# Digital_Interfaces.net
KiCad netlist of a schematic drawn in Altium Designer
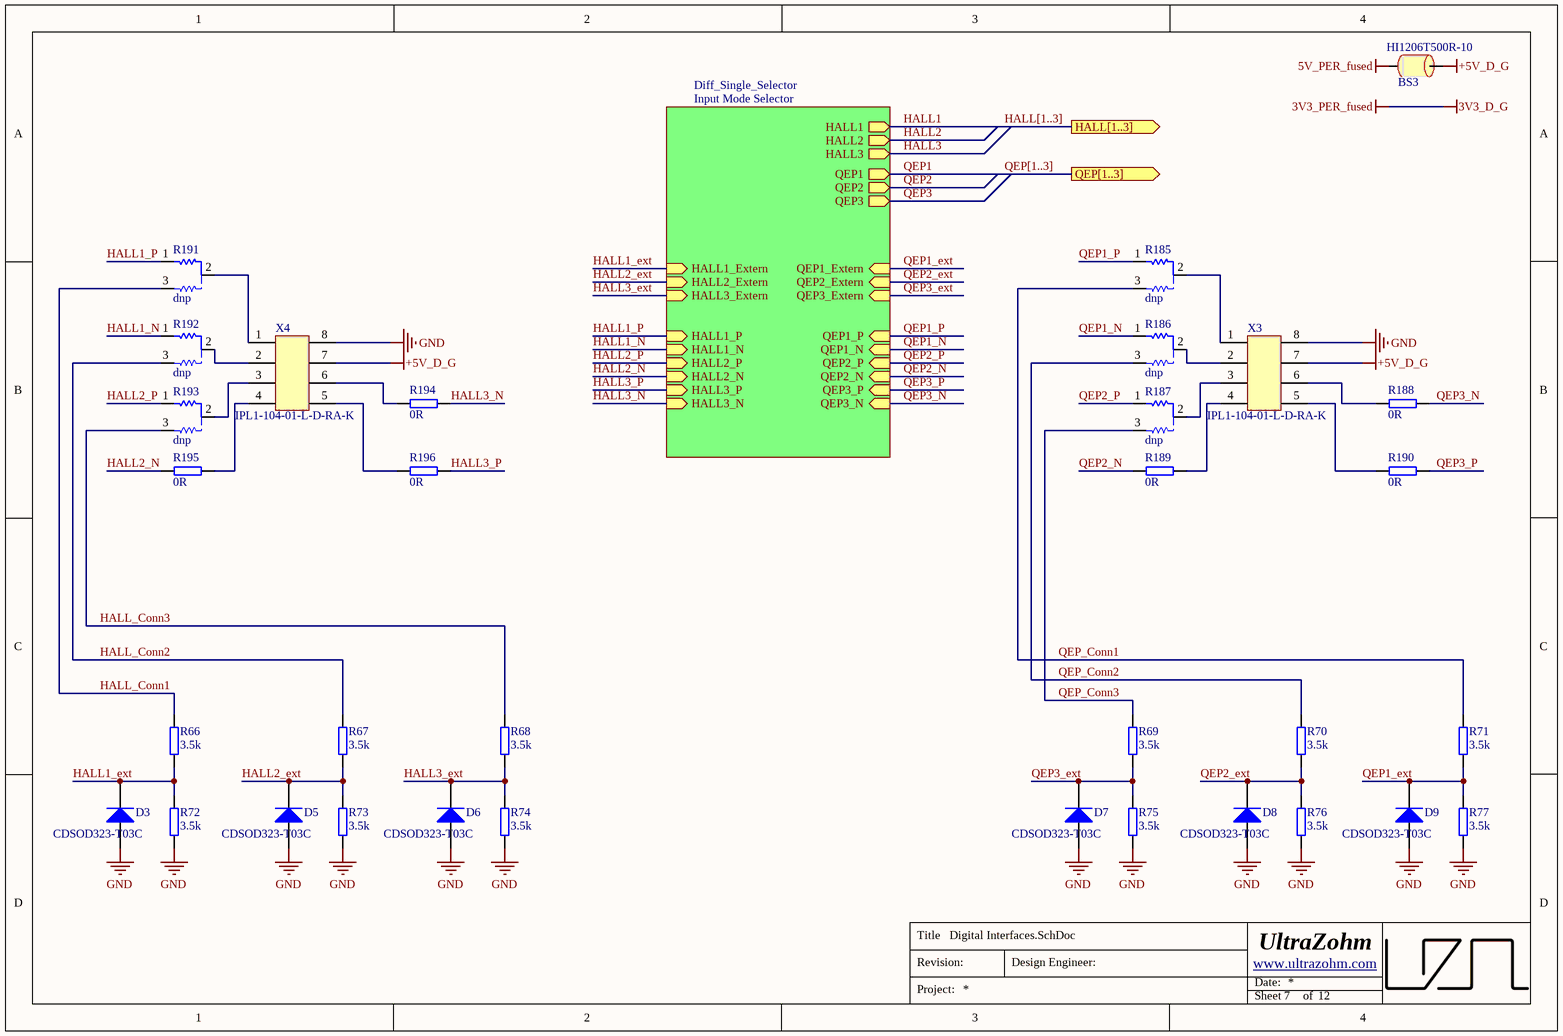
[diagram p0: Digital Interfaces.SchDoc]

(export (version "E")
  (design (tool "Eeschema 10.0.6"))
  (components
    (comp (ref "BS3")
      (value "HI1206T500R-10")
      (footprint "RES_1206")
      (description "Ferrite bead 6A")
      (fields (field (name "MF") "Laird"))
      (libsource (lib "Componentes_SOC") (part "Bead"))
    )
    (comp (ref "D3")
      (value "CDSOD323-T03C")
      (footprint "SOD-323")
      (description "TVS DIODE 3.3V 19V SOD323")
      (fields (field (name "MF") "Bourns"))
      (libsource (lib "Componentes_SOC") (part "Diodo TVS"))
    )
    (comp (ref "D5")
      (value "CDSOD323-T03C")
      (footprint "SOD-323")
      (description "TVS DIODE 3.3V 19V SOD323")
      (fields (field (name "MF") "Bourns"))
      (libsource (lib "Componentes_SOC") (part "Diodo TVS"))
    )
    (comp (ref "D6")
      (value "CDSOD323-T03C")
      (footprint "SOD-323")
      (description "TVS DIODE 3.3V 19V SOD323")
      (fields (field (name "MF") "Bourns"))
      (libsource (lib "Componentes_SOC") (part "Diodo TVS"))
    )
    (comp (ref "D7")
      (value "CDSOD323-T03C")
      (footprint "SOD-323")
      (description "TVS DIODE 3.3V 19V SOD323")
      (fields (field (name "MF") "Bourns"))
      (libsource (lib "Componentes_SOC") (part "Diodo TVS"))
    )
    (comp (ref "D8")
      (value "CDSOD323-T03C")
      (footprint "SOD-323")
      (description "TVS DIODE 3.3V 19V SOD323")
      (fields (field (name "MF") "Bourns"))
      (libsource (lib "Componentes_SOC") (part "Diodo TVS"))
    )
    (comp (ref "D9")
      (value "CDSOD323-T03C")
      (footprint "SOD-323")
      (description "TVS DIODE 3.3V 19V SOD323")
      (fields (field (name "MF") "Bourns"))
      (libsource (lib "Componentes_SOC") (part "Diodo TVS"))
    )
    (comp (ref "R66")
      (value "3.5k")
      (footprint "RESC1608X06N")
      (libsource (lib "UltraZohm_ADC") (part "R_0603"))
    )
    (comp (ref "R67")
      (value "3.5k")
      (footprint "RESC1608X06N")
      (libsource (lib "UltraZohm_ADC") (part "R_0603"))
    )
    (comp (ref "R68")
      (value "3.5k")
      (footprint "RESC1608X06N")
      (libsource (lib "UltraZohm_ADC") (part "R_0603"))
    )
    (comp (ref "R69")
      (value "3.5k")
      (footprint "RESC1608X06N")
      (libsource (lib "UltraZohm_ADC") (part "R_0603"))
    )
    (comp (ref "R70")
      (value "3.5k")
      (footprint "RESC1608X06N")
      (libsource (lib "UltraZohm_ADC") (part "R_0603"))
    )
    (comp (ref "R71")
      (value "3.5k")
      (footprint "RESC1608X06N")
      (libsource (lib "UltraZohm_ADC") (part "R_0603"))
    )
    (comp (ref "R72")
      (value "3.5k")
      (footprint "RESC1608X06N")
      (libsource (lib "UltraZohm_ADC") (part "R_0603"))
    )
    (comp (ref "R73")
      (value "3.5k")
      (footprint "RESC1608X06N")
      (libsource (lib "UltraZohm_ADC") (part "R_0603"))
    )
    (comp (ref "R74")
      (value "3.5k")
      (footprint "RESC1608X06N")
      (libsource (lib "UltraZohm_ADC") (part "R_0603"))
    )
    (comp (ref "R75")
      (value "3.5k")
      (footprint "RESC1608X06N")
      (libsource (lib "UltraZohm_ADC") (part "R_0603"))
    )
    (comp (ref "R76")
      (value "3.5k")
      (footprint "RESC1608X06N")
      (libsource (lib "UltraZohm_ADC") (part "R_0603"))
    )
    (comp (ref "R77")
      (value "3.5k")
      (footprint "RESC1608X06N")
      (libsource (lib "UltraZohm_ADC") (part "R_0603"))
    )
    (comp (ref "R185")
      (value "dnp")
      (footprint "0603_Config")
      (fields
        (field (name "MPN") "MCWR06X1002FTL")
        (field (name "MF") "Multicomp")
        (field (name "VOLTAGE") "50V")
        (field (name "CREATED") "2018_09_04_AGeiger")
      )
      (libsource (lib "Componentes_SOC") (part "R_config"))
    )
    (comp (ref "R186")
      (value "dnp")
      (footprint "0603_Config")
      (fields
        (field (name "MPN") "MCWR06X1002FTL")
        (field (name "MF") "Multicomp")
        (field (name "VOLTAGE") "50V")
        (field (name "CREATED") "2018_09_04_AGeiger")
      )
      (libsource (lib "Componentes_SOC") (part "R_config"))
    )
    (comp (ref "R187")
      (value "dnp")
      (footprint "0603_Config")
      (fields
        (field (name "MPN") "MCWR06X1002FTL")
        (field (name "MF") "Multicomp")
        (field (name "VOLTAGE") "50V")
        (field (name "CREATED") "2018_09_04_AGeiger")
      )
      (libsource (lib "Componentes_SOC") (part "R_config"))
    )
    (comp (ref "R188")
      (value "0R")
      (footprint "RESC1608X06N")
      (fields (field (name "MF") "Vishay") (field (name "MPN") "CRCW06030000Z0EAC"))
      (libsource (lib "UltraZohm_ADC") (part "R_0603"))
    )
    (comp (ref "R189")
      (value "0R")
      (footprint "RESC1608X06N")
      (fields (field (name "MF") "Vishay") (field (name "MPN") "CRCW06030000Z0EAC"))
      (libsource (lib "UltraZohm_ADC") (part "R_0603"))
    )
    (comp (ref "R190")
      (value "0R")
      (footprint "RESC1608X06N")
      (fields (field (name "MF") "Vishay") (field (name "MPN") "CRCW06030000Z0EAC"))
      (libsource (lib "UltraZohm_ADC") (part "R_0603"))
    )
    (comp (ref "R191")
      (value "dnp")
      (footprint "0603_Config")
      (fields
        (field (name "MPN") "MCWR06X1002FTL")
        (field (name "MF") "Multicomp")
        (field (name "VOLTAGE") "50V")
        (field (name "CREATED") "2018_09_04_AGeiger")
      )
      (libsource (lib "Componentes_SOC") (part "R_config"))
    )
    (comp (ref "R192")
      (value "dnp")
      (footprint "0603_Config")
      (fields
        (field (name "MPN") "MCWR06X1002FTL")
        (field (name "MF") "Multicomp")
        (field (name "VOLTAGE") "50V")
        (field (name "CREATED") "2018_09_04_AGeiger")
      )
      (libsource (lib "Componentes_SOC") (part "R_config"))
    )
    (comp (ref "R193")
      (value "dnp")
      (footprint "0603_Config")
      (fields
        (field (name "MPN") "MCWR06X1002FTL")
        (field (name "MF") "Multicomp")
        (field (name "VOLTAGE") "50V")
        (field (name "CREATED") "2018_09_04_AGeiger")
      )
      (libsource (lib "Componentes_SOC") (part "R_config"))
    )
    (comp (ref "R194")
      (value "0R")
      (footprint "RESC1608X06N")
      (fields (field (name "MF") "Vishay") (field (name "MPN") "CRCW06030000Z0EAC"))
      (libsource (lib "UltraZohm_ADC") (part "R_0603"))
    )
    (comp (ref "R195")
      (value "0R")
      (footprint "RESC1608X06N")
      (fields (field (name "MF") "Vishay") (field (name "MPN") "CRCW06030000Z0EAC"))
      (libsource (lib "UltraZohm_ADC") (part "R_0603"))
    )
    (comp (ref "R196")
      (value "0R")
      (footprint "RESC1608X06N")
      (fields (field (name "MF") "Vishay") (field (name "MPN") "CRCW06030000Z0EAC"))
      (libsource (lib "UltraZohm_ADC") (part "R_0603"))
    )
    (comp (ref "X3")
      (value "IPL1-104-01-L-D-RA-K")
      (footprint "Conector 4x2 TH Horizontal")
      (description "CONN HEADER R/A 8POS 2.54MM Through Hole")
      (fields (field (name "MF") "Samtec"))
      (libsource (lib "Componentes_SOC") (part "Conector 4x2 Horizontal"))
    )
    (comp (ref "X4")
      (value "IPL1-104-01-L-D-RA-K")
      (footprint "Conector 4x2 TH Horizontal")
      (description "CONN HEADER R/A 8POS 2.54MM Through Hole")
      (fields (field (name "MF") "Samtec"))
      (libsource (lib "Componentes_SOC") (part "Conector 4x2 Horizontal"))
    )
  )
  (nets
    (net (code "1") (name "+5V_D_G") (class "Default")
      (node (ref "BS3") (pin "1") (pintype "passive"))
      (node (ref "X3") (pin "7") (pintype "passive"))
      (node (ref "X4") (pin "7") (pintype "passive"))
    )
    (net (code "3") (name "/HALL1_N") (class "Default")
      (node (ref "R192") (pin "1") (pinfunction "1_1") (pintype "passive"))
    )
    (net (code "4") (name "/HALL1_P") (class "Default")
      (node (ref "R191") (pin "1") (pinfunction "1_1") (pintype "passive"))
    )
    (net (code "5") (name "/HALL1_ext") (class "Default")
      (node (ref "D3") (pin "1") (pinfunction "K_1") (pintype "passive"))
      (node (ref "R66") (pin "2") (pintype "passive"))
      (node (ref "R72") (pin "1") (pintype "passive"))
    )
    (net (code "7") (name "/HALL2_N") (class "Default") (node (ref "R195") (pin "1") (pintype "passive")))
    (net (code "8") (name "/HALL2_P") (class "Default")
      (node (ref "R193") (pin "1") (pinfunction "1_1") (pintype "passive"))
    )
    (net (code "9") (name "/HALL2_ext") (class "Default")
      (node (ref "D5") (pin "1") (pinfunction "K_1") (pintype "passive"))
      (node (ref "R67") (pin "2") (pintype "passive"))
      (node (ref "R73") (pin "1") (pintype "passive"))
    )
    (net (code "11") (name "/HALL3_N") (class "Default") (node (ref "R194") (pin "2") (pintype "passive")))
    (net (code "12") (name "/HALL3_P") (class "Default") (node (ref "R196") (pin "2") (pintype "passive")))
    (net (code "13") (name "/HALL3_ext") (class "Default")
      (node (ref "D6") (pin "1") (pinfunction "K_1") (pintype "passive"))
      (node (ref "R68") (pin "2") (pintype "passive"))
      (node (ref "R74") (pin "1") (pintype "passive"))
    )
    (net (code "15") (name "/HALL_Conn1") (class "Default")
      (node (ref "R191") (pin "3") (pinfunction "3_3") (pintype "passive"))
      (node (ref "R66") (pin "1") (pintype "passive"))
    )
    (net (code "16") (name "/HALL_Conn2") (class "Default")
      (node (ref "R192") (pin "3") (pinfunction "3_3") (pintype "passive"))
      (node (ref "R67") (pin "1") (pintype "passive"))
    )
    (net (code "17") (name "/HALL_Conn3") (class "Default")
      (node (ref "R193") (pin "3") (pinfunction "3_3") (pintype "passive"))
      (node (ref "R68") (pin "1") (pintype "passive"))
    )
    (net (code "19") (name "/QEP1_N") (class "Default")
      (node (ref "R186") (pin "1") (pinfunction "1_1") (pintype "passive"))
    )
    (net (code "20") (name "/QEP1_P") (class "Default")
      (node (ref "R185") (pin "1") (pinfunction "1_1") (pintype "passive"))
    )
    (net (code "21") (name "/QEP1_ext") (class "Default")
      (node (ref "D9") (pin "1") (pinfunction "K_1") (pintype "passive"))
      (node (ref "R71") (pin "2") (pintype "passive"))
      (node (ref "R77") (pin "1") (pintype "passive"))
    )
    (net (code "23") (name "/QEP2_N") (class "Default") (node (ref "R189") (pin "1") (pintype "passive")))
    (net (code "24") (name "/QEP2_P") (class "Default")
      (node (ref "R187") (pin "1") (pinfunction "1_1") (pintype "passive"))
    )
    (net (code "25") (name "/QEP2_ext") (class "Default")
      (node (ref "D8") (pin "1") (pinfunction "K_1") (pintype "passive"))
      (node (ref "R70") (pin "2") (pintype "passive"))
      (node (ref "R76") (pin "1") (pintype "passive"))
    )
    (net (code "27") (name "/QEP3_N") (class "Default") (node (ref "R188") (pin "2") (pintype "passive")))
    (net (code "28") (name "/QEP3_P") (class "Default") (node (ref "R190") (pin "2") (pintype "passive")))
    (net (code "29") (name "/QEP3_ext") (class "Default")
      (node (ref "D7") (pin "1") (pinfunction "K_1") (pintype "passive"))
      (node (ref "R69") (pin "2") (pintype "passive"))
      (node (ref "R75") (pin "1") (pintype "passive"))
    )
    (net (code "31") (name "/QEP_Conn1") (class "Default")
      (node (ref "R185") (pin "3") (pinfunction "3_3") (pintype "passive"))
      (node (ref "R71") (pin "1") (pintype "passive"))
    )
    (net (code "32") (name "/QEP_Conn2") (class "Default")
      (node (ref "R186") (pin "3") (pinfunction "3_3") (pintype "passive"))
      (node (ref "R70") (pin "1") (pintype "passive"))
    )
    (net (code "33") (name "/QEP_Conn3") (class "Default")
      (node (ref "R187") (pin "3") (pinfunction "3_3") (pintype "passive"))
      (node (ref "R69") (pin "1") (pintype "passive"))
    )
    (net (code "35") (name "5V_PER_fused") (class "Default") (node (ref "BS3") (pin "2") (pintype "passive")))
    (net (code "36") (name "GND") (class "Default")
      (node (ref "D3") (pin "2") (pinfunction "A_2") (pintype "passive"))
      (node (ref "D5") (pin "2") (pinfunction "A_2") (pintype "passive"))
      (node (ref "D6") (pin "2") (pinfunction "A_2") (pintype "passive"))
      (node (ref "D7") (pin "2") (pinfunction "A_2") (pintype "passive"))
      (node (ref "D8") (pin "2") (pinfunction "A_2") (pintype "passive"))
      (node (ref "D9") (pin "2") (pinfunction "A_2") (pintype "passive"))
      (node (ref "R72") (pin "2") (pintype "passive"))
      (node (ref "R73") (pin "2") (pintype "passive"))
      (node (ref "R74") (pin "2") (pintype "passive"))
      (node (ref "R75") (pin "2") (pintype "passive"))
      (node (ref "R76") (pin "2") (pintype "passive"))
      (node (ref "R77") (pin "2") (pintype "passive"))
      (node (ref "X3") (pin "8") (pintype "passive"))
      (node (ref "X4") (pin "8") (pintype "passive"))
    )
    (net (code "37") (name "Net-(R185-Pad2)") (class "Default")
      (node (ref "R185") (pin "2") (pinfunction "2_2") (pintype "passive"))
      (node (ref "X3") (pin "1") (pintype "passive"))
    )
    (net (code "38") (name "Net-(R186-Pad2)") (class "Default")
      (node (ref "R186") (pin "2") (pinfunction "2_2") (pintype "passive"))
      (node (ref "X3") (pin "2") (pintype "passive"))
    )
    (net (code "39") (name "Net-(R187-Pad2)") (class "Default")
      (node (ref "R187") (pin "2") (pinfunction "2_2") (pintype "passive"))
      (node (ref "X3") (pin "3") (pintype "passive"))
    )
    (net (code "40") (name "Net-(R188-Pad1)") (class "Default")
      (node (ref "R188") (pin "1") (pintype "passive"))
      (node (ref "X3") (pin "6") (pintype "passive"))
    )
    (net (code "41") (name "Net-(R189-Pad2)") (class "Default")
      (node (ref "R189") (pin "2") (pintype "passive"))
      (node (ref "X3") (pin "4") (pintype "passive"))
    )
    (net (code "42") (name "Net-(R190-Pad1)") (class "Default")
      (node (ref "R190") (pin "1") (pintype "passive"))
      (node (ref "X3") (pin "5") (pintype "passive"))
    )
    (net (code "43") (name "Net-(R191-Pad2)") (class "Default")
      (node (ref "R191") (pin "2") (pinfunction "2_2") (pintype "passive"))
      (node (ref "X4") (pin "1") (pintype "passive"))
    )
    (net (code "44") (name "Net-(R192-Pad2)") (class "Default")
      (node (ref "R192") (pin "2") (pinfunction "2_2") (pintype "passive"))
      (node (ref "X4") (pin "2") (pintype "passive"))
    )
    (net (code "45") (name "Net-(R193-Pad2)") (class "Default")
      (node (ref "R193") (pin "2") (pinfunction "2_2") (pintype "passive"))
      (node (ref "X4") (pin "3") (pintype "passive"))
    )
    (net (code "46") (name "Net-(R194-Pad1)") (class "Default")
      (node (ref "R194") (pin "1") (pintype "passive"))
      (node (ref "X4") (pin "6") (pintype "passive"))
    )
    (net (code "47") (name "Net-(R195-Pad2)") (class "Default")
      (node (ref "R195") (pin "2") (pintype "passive"))
      (node (ref "X4") (pin "4") (pintype "passive"))
    )
    (net (code "48") (name "Net-(R196-Pad1)") (class "Default")
      (node (ref "R196") (pin "1") (pintype "passive"))
      (node (ref "X4") (pin "5") (pintype "passive"))
    )
  )
)
